# RaspberryMesh.net
KiCad netlist of a schematic drawn in EAGLE
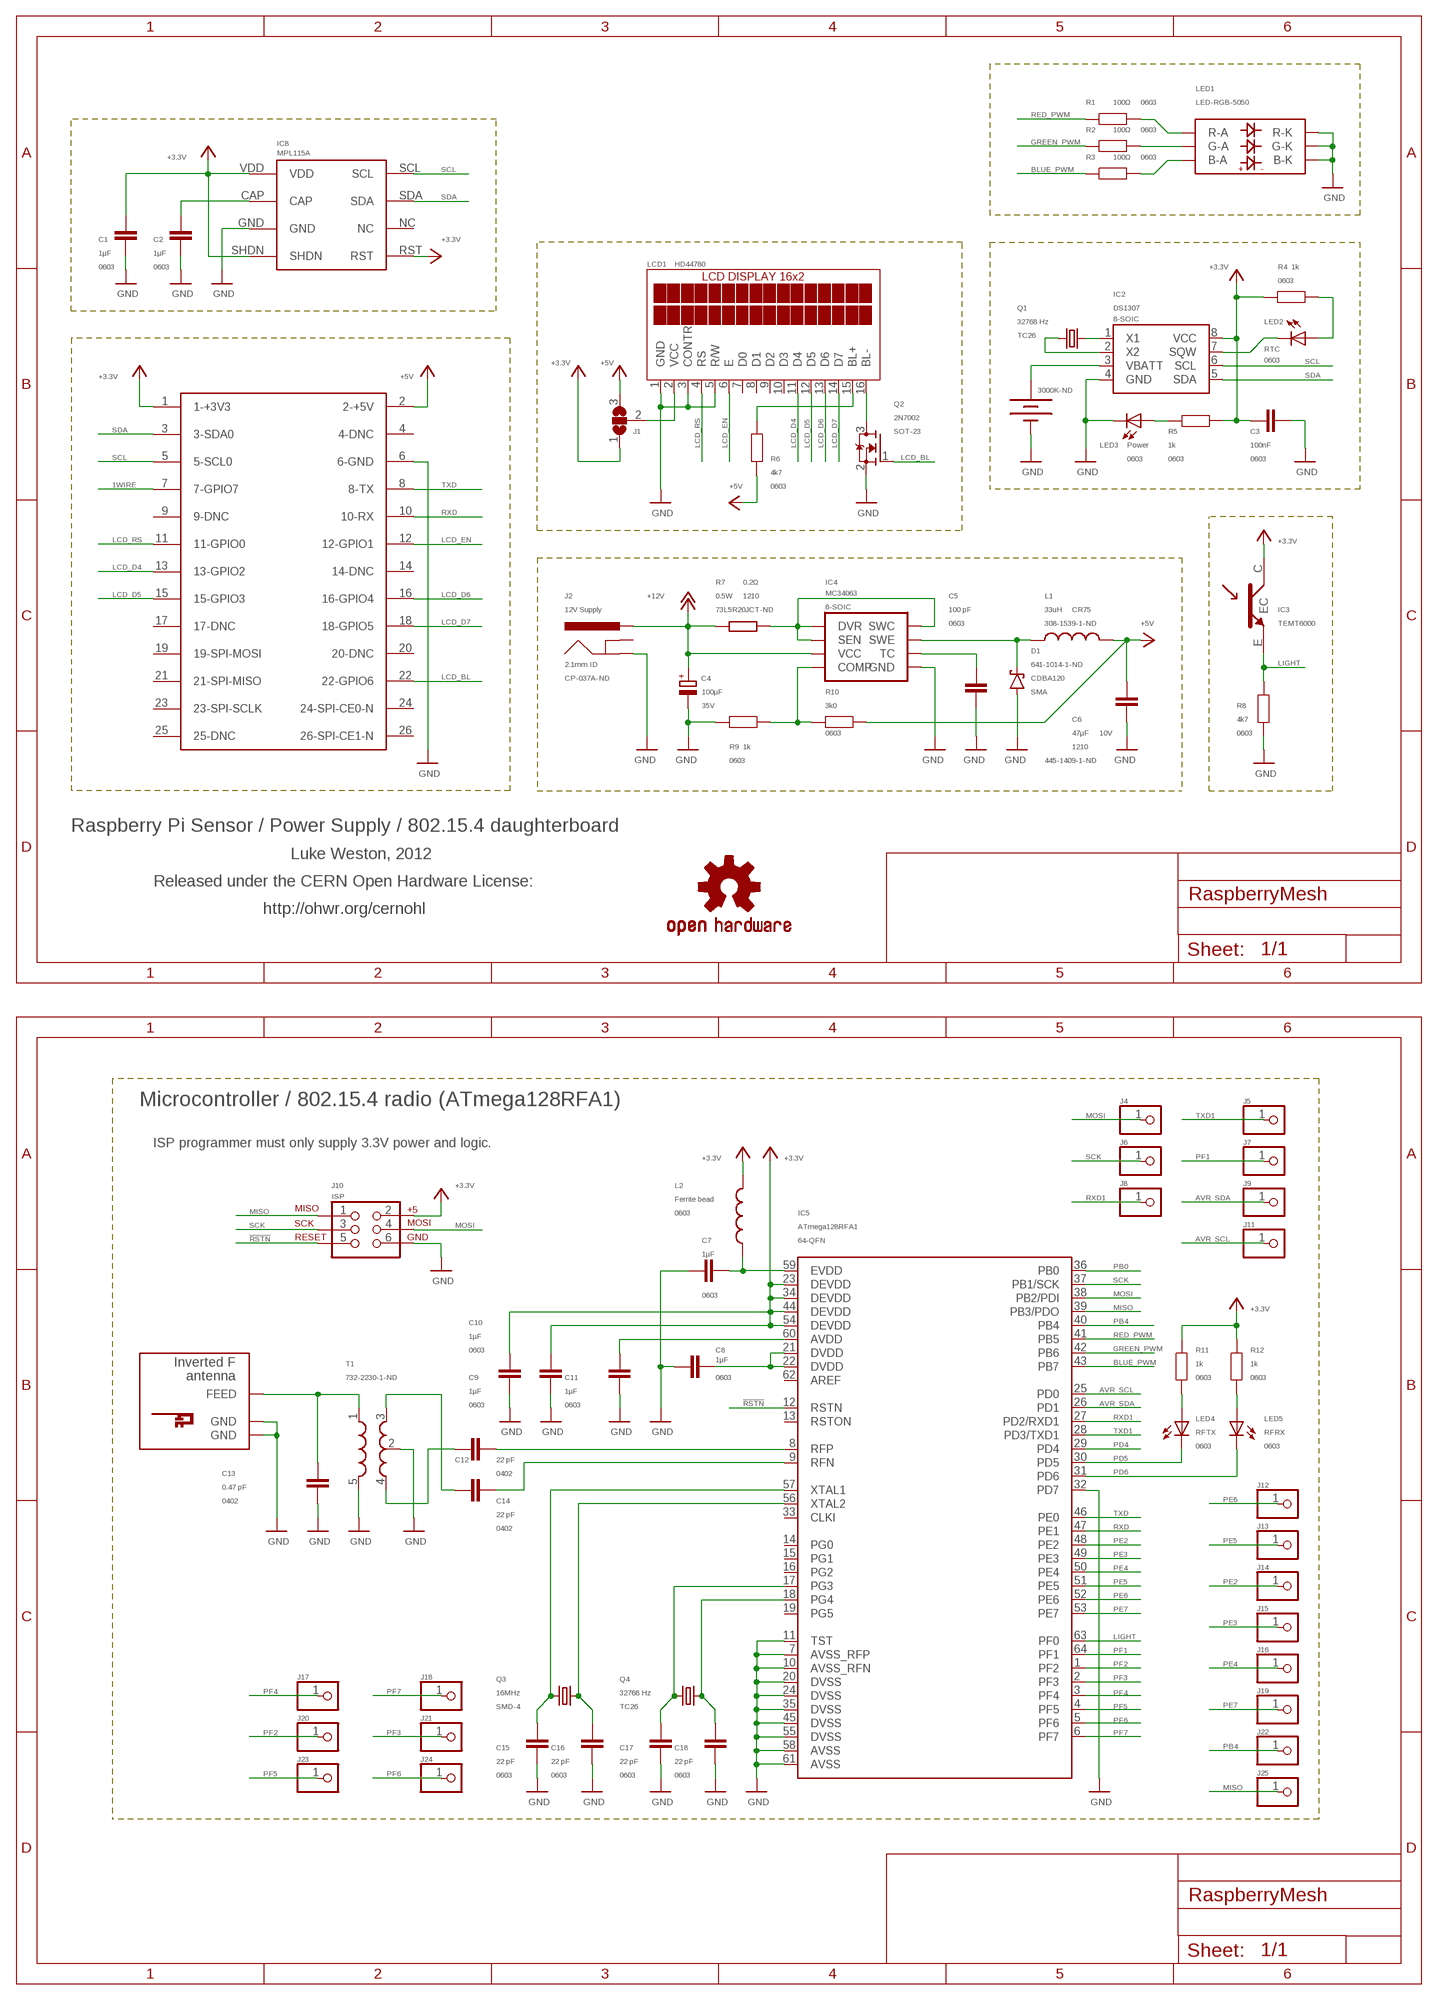
[diagram p0: schematic, sheet 1]

(export (version "E")
  (design (tool "Eeschema 10.0.6"))
  (components
    (comp (ref "A1")
      (value "INVERTED_F_ANTENNA+2")
      (footprint "eagle-import:DN007+2")
      (libsource (lib "eagle-import") (part "INVERTED_F_ANTENNA+2"))
    )
    (comp (ref "B1")
      (value "3000K-ND")
      (footprint "eagle-import:BATTCON_12MM")
      (libsource (lib "eagle-import") (part "BATTERY12MM"))
    )
    (comp (ref "C1")
      (value "1µF")
      (footprint "eagle-import:0603")
      (fields (field (name "PACKAGE") "0603"))
      (libsource (lib "eagle-import") (part "CAP0603"))
    )
    (comp (ref "C2")
      (value "1µF")
      (footprint "eagle-import:0603")
      (fields (field (name "PACKAGE") "0603"))
      (libsource (lib "eagle-import") (part "CAP0603"))
    )
    (comp (ref "C3")
      (value "100nF")
      (footprint "eagle-import:0603")
      (fields (field (name "PACKAGE") "0603"))
      (libsource (lib "eagle-import") (part "CAP0603"))
    )
    (comp (ref "C4")
      (value "100µF")
      (footprint "eagle-import:E2,5-6")
      (fields (field (name "VOLTAGE") "35V"))
      (libsource (lib "eagle-import") (part "CPOL-EUE2.5-6"))
    )
    (comp (ref "C5")
      (value "100 pF")
      (footprint "eagle-import:0603")
      (fields (field (name "PACKAGE") "0603"))
      (libsource (lib "eagle-import") (part "CAP0603"))
    )
    (comp (ref "C6")
      (value "47µF")
      (footprint "eagle-import:C1210")
      (fields
        (field (name "PACKAGE") "1210")
        (field (name "SKU") "445-1409-1-ND")
        (field (name "VOLTAGE") "10V")
      )
      (libsource (lib "eagle-import") (part "C-EUC1210"))
    )
    (comp (ref "C7")
      (value "1µF")
      (footprint "eagle-import:0603")
      (fields (field (name "PACKAGE") "0603"))
      (libsource (lib "eagle-import") (part "CAP0603"))
    )
    (comp (ref "C8")
      (value "1µF")
      (footprint "eagle-import:0603")
      (fields (field (name "PACKAGE") "0603"))
      (libsource (lib "eagle-import") (part "CAP0603"))
    )
    (comp (ref "C9")
      (value "1µF")
      (footprint "eagle-import:0603")
      (fields (field (name "PACKAGE") "0603"))
      (libsource (lib "eagle-import") (part "CAP0603"))
    )
    (comp (ref "C10")
      (value "1µF")
      (footprint "eagle-import:0603")
      (fields (field (name "PACKAGE") "0603"))
      (libsource (lib "eagle-import") (part "CAP0603"))
    )
    (comp (ref "C11")
      (value "1µF")
      (footprint "eagle-import:0603")
      (fields (field (name "PACKAGE") "0603"))
      (libsource (lib "eagle-import") (part "CAP0603"))
    )
    (comp (ref "C12")
      (value "22 pF")
      (footprint "eagle-import:C0402")
      (fields (field (name "PACKAGE") "0402"))
      (libsource (lib "eagle-import") (part "CAP0402"))
    )
    (comp (ref "C13")
      (value "0.47 pF")
      (footprint "eagle-import:C0402")
      (fields (field (name "PACKAGE") "0402"))
      (libsource (lib "eagle-import") (part "CAP0402"))
    )
    (comp (ref "C14")
      (value "22 pF")
      (footprint "eagle-import:C0402")
      (fields (field (name "PACKAGE") "0402"))
      (libsource (lib "eagle-import") (part "CAP0402"))
    )
    (comp (ref "C15")
      (value "22 pF")
      (footprint "eagle-import:0603")
      (fields (field (name "PACKAGE") "0603"))
      (libsource (lib "eagle-import") (part "CAP0603"))
    )
    (comp (ref "C16")
      (value "22 pF")
      (footprint "eagle-import:0603")
      (fields (field (name "PACKAGE") "0603"))
      (libsource (lib "eagle-import") (part "CAP0603"))
    )
    (comp (ref "C17")
      (value "22 pF")
      (footprint "eagle-import:0603")
      (fields (field (name "PACKAGE") "0603"))
      (libsource (lib "eagle-import") (part "CAP0603"))
    )
    (comp (ref "C18")
      (value "22 pF")
      (footprint "eagle-import:0603")
      (fields (field (name "PACKAGE") "0603"))
      (libsource (lib "eagle-import") (part "CAP0603"))
    )
    (comp (ref "D1")
      (value "CDBA120")
      (footprint "eagle-import:SMA")
      (fields (field (name "PACKAGE") "SMA") (field (name "SKU") "641-1014-1-ND"))
      (libsource (lib "eagle-import") (part "SCHOTTKY"))
    )
    (comp (ref "IC1")
      (value "MPL115A")
      (footprint "eagle-import:MPL115A")
      (fields (field (name "NAME2") "IC8") (field (name "VALUE2") "MPL115A"))
      (libsource (lib "eagle-import") (part "MPL115A"))
    )
    (comp (ref "IC2")
      (value "DS1307")
      (footprint "eagle-import:SO08")
      (fields (field (name "PACKAGE") "8-SOIC"))
      (libsource (lib "eagle-import") (part "DS1307SO8"))
    )
    (comp (ref "IC3")
      (value "TEMT6000")
      (footprint "eagle-import:TEMT6000")
      (libsource (lib "eagle-import") (part "TEMT6000SMT"))
    )
    (comp (ref "IC4")
      (value "MC34063")
      (footprint "eagle-import:SO08@1")
      (fields (field (name "PACKAGE") "8-SOIC"))
      (libsource (lib "eagle-import") (part "MC34063SMD"))
    )
    (comp (ref "IC5")
      (value "ATmega128RFA1")
      (footprint "eagle-import:QFN-64")
      (fields (field (name "PACKAGE") "64-QFN"))
      (libsource (lib "eagle-import") (part "ATMEGA128RFA1"))
    )
    (comp (ref "J1")
      (value "SJ2W")
      (footprint "eagle-import:SJ_2")
      (libsource (lib "eagle-import") (part "SJ2W"))
    )
    (comp (ref "J2")
      (value "12V Supply")
      (footprint "eagle-import:POWER_JACK_SLOT")
      (fields (field (name "DIAMETER") "2.1mm ID") (field (name "SKU") "CP-037A-ND"))
      (libsource (lib "eagle-import") (part "POWER_JACKSLT"))
    )
    (comp (ref "J3")
      (value "RASPBERRY-PI")
      (footprint "eagle-import:RASPBERRY-PI")
      (libsource (lib "eagle-import") (part "RASPBERRY-PI"))
    )
    (comp (ref "J4")
      (value "PINHD-1X1")
      (footprint "eagle-import:1X01")
      (libsource (lib "eagle-import") (part "PINHD-1X1"))
    )
    (comp (ref "J5")
      (value "PINHD-1X1")
      (footprint "eagle-import:1X01")
      (libsource (lib "eagle-import") (part "PINHD-1X1"))
    )
    (comp (ref "J6")
      (value "PINHD-1X1")
      (footprint "eagle-import:1X01")
      (libsource (lib "eagle-import") (part "PINHD-1X1"))
    )
    (comp (ref "J7")
      (value "PINHD-1X1")
      (footprint "eagle-import:1X01")
      (libsource (lib "eagle-import") (part "PINHD-1X1"))
    )
    (comp (ref "J8")
      (value "PINHD-1X1")
      (footprint "eagle-import:1X01")
      (libsource (lib "eagle-import") (part "PINHD-1X1"))
    )
    (comp (ref "J9")
      (value "PINHD-1X1")
      (footprint "eagle-import:1X01")
      (libsource (lib "eagle-import") (part "PINHD-1X1"))
    )
    (comp (ref "J10")
      (value "ISP")
      (footprint "eagle-import:2X3-NS")
      (libsource (lib "eagle-import") (part "AVR_SPI_PRG_6NS"))
    )
    (comp (ref "J11")
      (value "PINHD-1X1")
      (footprint "eagle-import:1X01")
      (libsource (lib "eagle-import") (part "PINHD-1X1"))
    )
    (comp (ref "J12")
      (value "PINHD-1X1")
      (footprint "eagle-import:1X01")
      (libsource (lib "eagle-import") (part "PINHD-1X1"))
    )
    (comp (ref "J13")
      (value "PINHD-1X1")
      (footprint "eagle-import:1X01")
      (libsource (lib "eagle-import") (part "PINHD-1X1"))
    )
    (comp (ref "J14")
      (value "PINHD-1X1")
      (footprint "eagle-import:1X01")
      (libsource (lib "eagle-import") (part "PINHD-1X1"))
    )
    (comp (ref "J15")
      (value "PINHD-1X1")
      (footprint "eagle-import:1X01")
      (libsource (lib "eagle-import") (part "PINHD-1X1"))
    )
    (comp (ref "J16")
      (value "PINHD-1X1")
      (footprint "eagle-import:1X01")
      (libsource (lib "eagle-import") (part "PINHD-1X1"))
    )
    (comp (ref "J17")
      (value "PINHD-1X1")
      (footprint "eagle-import:1X01")
      (libsource (lib "eagle-import") (part "PINHD-1X1"))
    )
    (comp (ref "J18")
      (value "PINHD-1X1")
      (footprint "eagle-import:1X01")
      (libsource (lib "eagle-import") (part "PINHD-1X1"))
    )
    (comp (ref "J19")
      (value "PINHD-1X1")
      (footprint "eagle-import:1X01")
      (libsource (lib "eagle-import") (part "PINHD-1X1"))
    )
    (comp (ref "J20")
      (value "PINHD-1X1")
      (footprint "eagle-import:1X01")
      (libsource (lib "eagle-import") (part "PINHD-1X1"))
    )
    (comp (ref "J21")
      (value "PINHD-1X1")
      (footprint "eagle-import:1X01")
      (libsource (lib "eagle-import") (part "PINHD-1X1"))
    )
    (comp (ref "J22")
      (value "PINHD-1X1")
      (footprint "eagle-import:1X01")
      (libsource (lib "eagle-import") (part "PINHD-1X1"))
    )
    (comp (ref "J23")
      (value "PINHD-1X1")
      (footprint "eagle-import:1X01")
      (libsource (lib "eagle-import") (part "PINHD-1X1"))
    )
    (comp (ref "J24")
      (value "PINHD-1X1")
      (footprint "eagle-import:1X01")
      (libsource (lib "eagle-import") (part "PINHD-1X1"))
    )
    (comp (ref "J25")
      (value "PINHD-1X1")
      (footprint "eagle-import:1X01")
      (libsource (lib "eagle-import") (part "PINHD-1X1"))
    )
    (comp (ref "L1")
      (value "33uH")
      (footprint "eagle-import:CR75")
      (fields (field (name "PACKAGE") "CR75") (field (name "SKU") "308-1539-1-ND"))
      (libsource (lib "eagle-import") (part "INDUCTORCR75"))
    )
    (comp (ref "L2")
      (value "Ferrite bead")
      (footprint "eagle-import:0603")
      (fields (field (name "PACKAGE") "0603"))
      (libsource (lib "eagle-import") (part "freetronics-master-v1_INDUCTOR0603"))
    )
    (comp (ref "LCD1")
      (value "HD44780")
      (footprint "eagle-import:LCD_16X2_REAR")
      (libsource (lib "eagle-import") (part "LCD_16X2_NEWLCD_16X2"))
    )
    (comp (ref "LED1")
      (value "LED-RGB-5050")
      (footprint "eagle-import:LED-RGB-5050")
      (libsource (lib "eagle-import") (part "LED-RGB-50505050"))
    )
    (comp (ref "LED2")
      (value "RTC")
      (footprint "eagle-import:LED-0603")
      (fields (field (name "PACKAGE") "0603"))
      (libsource (lib "eagle-import") (part "LED0603"))
    )
    (comp (ref "LED3")
      (value "Power")
      (footprint "eagle-import:LED-0603")
      (fields (field (name "PACKAGE") "0603"))
      (libsource (lib "eagle-import") (part "LED0603"))
    )
    (comp (ref "LED4")
      (value "RFTX")
      (footprint "eagle-import:LED-0603")
      (fields (field (name "PACKAGE") "0603"))
      (libsource (lib "eagle-import") (part "LED0603"))
    )
    (comp (ref "LED5")
      (value "RFRX")
      (footprint "eagle-import:LED-0603")
      (fields (field (name "PACKAGE") "0603"))
      (libsource (lib "eagle-import") (part "LED0603"))
    )
    (comp (ref "Q1")
      (value "32768 Hz")
      (footprint "eagle-import:CRYSTAL-32KHZ-SMD")
      (fields (field (name "PACKAGE") "TC26"))
      (libsource (lib "eagle-import") (part "CRYSTAL32-SMD"))
    )
    (comp (ref "Q2")
      (value "2N7002")
      (footprint "eagle-import:SOT23")
      (fields (field (name "PACKAGE") "SOT-23"))
      (libsource (lib "eagle-import") (part "MOSFET-NREFLOW"))
    )
    (comp (ref "Q3")
      (value "16MHz")
      (footprint "eagle-import:CRYSTAL-SMD-5X3")
      (fields (field (name "PACKAGE") "SMD-4"))
      (libsource (lib "eagle-import") (part "CRYSTAL5X3"))
    )
    (comp (ref "Q4")
      (value "32768 Hz")
      (footprint "eagle-import:CRYSTAL-32KHZ-SMD")
      (fields (field (name "PACKAGE") "TC26"))
      (libsource (lib "eagle-import") (part "CRYSTAL32-SMD"))
    )
    (comp (ref "R1")
      (value "100Ω")
      (footprint "eagle-import:0603")
      (fields (field (name "PACKAGE") "0603"))
      (libsource (lib "eagle-import") (part "RESISTOR0603"))
    )
    (comp (ref "R2")
      (value "100Ω")
      (footprint "eagle-import:0603")
      (fields (field (name "PACKAGE") "0603"))
      (libsource (lib "eagle-import") (part "RESISTOR0603"))
    )
    (comp (ref "R3")
      (value "100Ω")
      (footprint "eagle-import:0603")
      (fields (field (name "PACKAGE") "0603"))
      (libsource (lib "eagle-import") (part "RESISTOR0603"))
    )
    (comp (ref "R4")
      (value "1k")
      (footprint "eagle-import:0603")
      (fields (field (name "PACKAGE") "0603"))
      (libsource (lib "eagle-import") (part "RESISTOR0603"))
    )
    (comp (ref "R5")
      (value "1k")
      (footprint "eagle-import:0603")
      (fields (field (name "PACKAGE") "0603"))
      (libsource (lib "eagle-import") (part "RESISTOR0603"))
    )
    (comp (ref "R6")
      (value "4k7")
      (footprint "eagle-import:0603")
      (fields (field (name "PACKAGE") "0603"))
      (libsource (lib "eagle-import") (part "RESISTOR0603"))
    )
    (comp (ref "R7")
      (value "0.2Ω")
      (footprint "eagle-import:R1210")
      (fields
        (field (name "PACKAGE") "1210")
        (field (name "POWER") "0.5W")
        (field (name "SKU") "73L5R20JCT-ND")
      )
      (libsource (lib "eagle-import") (part "R-EU_R1210"))
    )
    (comp (ref "R8")
      (value "4k7")
      (footprint "eagle-import:0603")
      (fields (field (name "PACKAGE") "0603"))
      (libsource (lib "eagle-import") (part "RESISTOR0603"))
    )
    (comp (ref "R9")
      (value "1k")
      (footprint "eagle-import:0603")
      (fields (field (name "PACKAGE") "0603"))
      (libsource (lib "eagle-import") (part "RESISTOR0603"))
    )
    (comp (ref "R10")
      (value "3k0")
      (footprint "eagle-import:0603")
      (fields (field (name "PACKAGE") "0603"))
      (libsource (lib "eagle-import") (part "RESISTOR0603"))
    )
    (comp (ref "R11")
      (value "1k")
      (footprint "eagle-import:0603")
      (fields (field (name "PACKAGE") "0603"))
      (libsource (lib "eagle-import") (part "RESISTOR0603"))
    )
    (comp (ref "R12")
      (value "1k")
      (footprint "eagle-import:0603")
      (fields (field (name "PACKAGE") "0603"))
      (libsource (lib "eagle-import") (part "RESISTOR0603"))
    )
    (comp (ref "SY1")
      (value "OSHW-LOGOS")
      (footprint "eagle-import:OSHW-LOGO-S")
      (libsource (lib "eagle-import") (part "OSHW-LOGOS"))
    )
    (comp (ref "T1")
      (value "732-2230-1-ND")
      (footprint "eagle-import:BALUN")
      (libsource (lib "eagle-import") (part "BALUN0805"))
    )
  )
  (nets
    (net (code "1") (name "+3.3V") (class "Default")
      (node (ref "C1") (pin "2") (pinfunction "2_2") (pintype "passive"))
      (node (ref "C10") (pin "1") (pinfunction "1_1") (pintype "passive"))
      (node (ref "C3") (pin "1") (pinfunction "1_1") (pintype "passive"))
      (node (ref "C9") (pin "1") (pinfunction "1_1") (pintype "passive"))
      (node (ref "IC1") (pin "RST") (pinfunction "RST_RST") (pintype "bidirectional"))
      (node (ref "IC1") (pin "SHDN") (pinfunction "SHDN_SHDN") (pintype "bidirectional"))
      (node (ref "IC1") (pin "VDD") (pinfunction "VDD_VDD") (pintype "bidirectional"))
      (node (ref "IC2") (pin "8") (pinfunction "VCC_8") (pintype "bidirectional"))
      (node (ref "IC3") (pin "C") (pinfunction "C_C") (pintype "bidirectional"))
      (node (ref "IC5") (pin "23") (pinfunction "DEVDD_23") (pintype "bidirectional"))
      (node (ref "IC5") (pin "34") (pinfunction "DEVDD_34") (pintype "bidirectional"))
      (node (ref "IC5") (pin "44") (pinfunction "DEVDD_44") (pintype "bidirectional"))
      (node (ref "IC5") (pin "54") (pinfunction "DEVDD_54") (pintype "bidirectional"))
      (node (ref "J1") (pin "1") (pinfunction "1_1") (pintype "passive"))
      (node (ref "J10") (pin "2") (pinfunction "2_2") (pintype "passive"))
      (node (ref "J3") (pin "1") (pinfunction "1-+3V3_1") (pintype "bidirectional"))
      (node (ref "L2") (pin "2") (pinfunction "2_2") (pintype "passive"))
      (node (ref "R11") (pin "2") (pinfunction "2_2") (pintype "passive"))
      (node (ref "R12") (pin "2") (pinfunction "2_2") (pintype "passive"))
      (node (ref "R4") (pin "2") (pinfunction "2_2") (pintype "passive"))
      (node (ref "R5") (pin "2") (pinfunction "2_2") (pintype "passive"))
    )
    (net (code "2") (name "+5V") (class "Default")
      (node (ref "C6") (pin "1") (pinfunction "1_1") (pintype "passive"))
      (node (ref "J1") (pin "3") (pinfunction "3_3") (pintype "passive"))
      (node (ref "J3") (pin "2") (pinfunction "2-+5V_2") (pintype "bidirectional"))
      (node (ref "L1") (pin "P$2") (pinfunction "2_P$2") (pintype "passive"))
      (node (ref "R10") (pin "1") (pinfunction "1_1") (pintype "passive"))
      (node (ref "R6") (pin "2") (pinfunction "2_2") (pintype "passive"))
    )
    (net (code "3") (name "+12V") (class "Default")
      (node (ref "C4") (pin "+") (pinfunction "+_+") (pintype "passive"))
      (node (ref "IC4") (pin "6") (pinfunction "VCC_6") (pintype "bidirectional"))
      (node (ref "J2") (pin "PWR") (pinfunction "PWR_PWR") (pintype "bidirectional"))
      (node (ref "R7") (pin "1") (pinfunction "1_1") (pintype "passive"))
    )
    (net (code "4") (name "/1WIRE") (class "Default")
      (node (ref "J3") (pin "7") (pinfunction "7-GPIO7_7") (pintype "bidirectional"))
    )
    (net (code "5") (name "/AVR_SCL") (class "Default")
      (node (ref "IC5") (pin "25") (pinfunction "PD0_25") (pintype "bidirectional"))
      (node (ref "J11") (pin "1") (pinfunction "1_1") (pintype "passive"))
    )
    (net (code "6") (name "/AVR_SDA") (class "Default")
      (node (ref "IC5") (pin "26") (pinfunction "PD1_26") (pintype "bidirectional"))
      (node (ref "J9") (pin "1") (pinfunction "1_1") (pintype "passive"))
    )
    (net (code "7") (name "/BLUE_PWM") (class "Default")
      (node (ref "IC5") (pin "43") (pinfunction "PB7_43") (pintype "bidirectional"))
      (node (ref "R3") (pin "2") (pinfunction "2_2") (pintype "passive"))
    )
    (net (code "8") (name "/GREEN_PWM") (class "Default")
      (node (ref "IC5") (pin "42") (pinfunction "PB6_42") (pintype "bidirectional"))
      (node (ref "R2") (pin "2") (pinfunction "2_2") (pintype "passive"))
    )
    (net (code "9") (name "/LCD_BL") (class "Default")
      (node (ref "J3") (pin "22") (pinfunction "22-GPIO6_22") (pintype "bidirectional"))
      (node (ref "Q2") (pin "1") (pinfunction "G_1") (pintype "bidirectional"))
    )
    (net (code "10") (name "/LCD_D4") (class "Default")
      (node (ref "J3") (pin "13") (pinfunction "13-GPIO2_13") (pintype "bidirectional"))
      (node (ref "LCD1") (pin "11") (pinfunction "D4_11") (pintype "input"))
    )
    (net (code "11") (name "/LCD_D5") (class "Default")
      (node (ref "J3") (pin "15") (pinfunction "15-GPIO3_15") (pintype "bidirectional"))
      (node (ref "LCD1") (pin "12") (pinfunction "D5_12") (pintype "input"))
    )
    (net (code "12") (name "/LCD_D6") (class "Default")
      (node (ref "J3") (pin "16") (pinfunction "16-GPIO4_16") (pintype "bidirectional"))
      (node (ref "LCD1") (pin "13") (pinfunction "D6_13") (pintype "input"))
    )
    (net (code "13") (name "/LCD_D7") (class "Default")
      (node (ref "J3") (pin "18") (pinfunction "18-GPIO5_18") (pintype "bidirectional"))
      (node (ref "LCD1") (pin "14") (pinfunction "D7_14") (pintype "input"))
    )
    (net (code "14") (name "/LCD_EN") (class "Default")
      (node (ref "J3") (pin "12") (pinfunction "12-GPIO1_12") (pintype "bidirectional"))
      (node (ref "LCD1") (pin "6") (pinfunction "E_6") (pintype "input"))
    )
    (net (code "15") (name "/LCD_RS") (class "Default")
      (node (ref "J3") (pin "11") (pinfunction "11-GPIO0_11") (pintype "bidirectional"))
      (node (ref "LCD1") (pin "4") (pinfunction "RS_4") (pintype "input"))
    )
    (net (code "16") (name "/LIGHT") (class "Default")
      (node (ref "IC3") (pin "E") (pinfunction "E_E") (pintype "bidirectional"))
      (node (ref "IC5") (pin "63") (pinfunction "PF0_63") (pintype "bidirectional"))
      (node (ref "R8") (pin "2") (pinfunction "2_2") (pintype "passive"))
    )
    (net (code "17") (name "/MISO") (class "Default")
      (node (ref "IC5") (pin "39") (pinfunction "PB3/PDO_39") (pintype "bidirectional"))
      (node (ref "J10") (pin "1") (pinfunction "1_1") (pintype "passive"))
      (node (ref "J25") (pin "1") (pinfunction "1_1") (pintype "passive"))
    )
    (net (code "18") (name "/MOSI") (class "Default")
      (node (ref "IC5") (pin "38") (pinfunction "PB2/PDI_38") (pintype "bidirectional"))
      (node (ref "J10") (pin "4") (pinfunction "4_4") (pintype "passive"))
      (node (ref "J4") (pin "1") (pinfunction "1_1") (pintype "passive"))
    )
    (net (code "19") (name "/PB0") (class "Default")
      (node (ref "IC5") (pin "36") (pinfunction "PB0_36") (pintype "bidirectional"))
    )
    (net (code "20") (name "/PB4") (class "Default")
      (node (ref "IC5") (pin "40") (pinfunction "PB4_40") (pintype "bidirectional"))
      (node (ref "J22") (pin "1") (pinfunction "1_1") (pintype "passive"))
    )
    (net (code "21") (name "/PD4") (class "Default")
      (node (ref "IC5") (pin "29") (pinfunction "PD4_29") (pintype "bidirectional"))
    )
    (net (code "22") (name "/PD5") (class "Default")
      (node (ref "IC5") (pin "30") (pinfunction "PD5_30") (pintype "bidirectional"))
      (node (ref "LED4") (pin "C") (pinfunction "C_C") (pintype "passive"))
    )
    (net (code "23") (name "/PD6") (class "Default")
      (node (ref "IC5") (pin "31") (pinfunction "PD6_31") (pintype "bidirectional"))
      (node (ref "LED5") (pin "C") (pinfunction "C_C") (pintype "passive"))
    )
    (net (code "24") (name "/PE2") (class "Default")
      (node (ref "IC5") (pin "48") (pinfunction "PE2_48") (pintype "bidirectional"))
      (node (ref "J14") (pin "1") (pinfunction "1_1") (pintype "passive"))
    )
    (net (code "25") (name "/PE3") (class "Default")
      (node (ref "IC5") (pin "49") (pinfunction "PE3_49") (pintype "bidirectional"))
      (node (ref "J15") (pin "1") (pinfunction "1_1") (pintype "passive"))
    )
    (net (code "26") (name "/PE4") (class "Default")
      (node (ref "IC5") (pin "50") (pinfunction "PE4_50") (pintype "bidirectional"))
      (node (ref "J16") (pin "1") (pinfunction "1_1") (pintype "passive"))
    )
    (net (code "27") (name "/PE5") (class "Default")
      (node (ref "IC5") (pin "51") (pinfunction "PE5_51") (pintype "bidirectional"))
      (node (ref "J13") (pin "1") (pinfunction "1_1") (pintype "passive"))
    )
    (net (code "28") (name "/PE6") (class "Default")
      (node (ref "IC5") (pin "52") (pinfunction "PE6_52") (pintype "bidirectional"))
      (node (ref "J12") (pin "1") (pinfunction "1_1") (pintype "passive"))
    )
    (net (code "29") (name "/PE7") (class "Default")
      (node (ref "IC5") (pin "53") (pinfunction "PE7_53") (pintype "bidirectional"))
      (node (ref "J19") (pin "1") (pinfunction "1_1") (pintype "passive"))
    )
    (net (code "30") (name "/PF1") (class "Default")
      (node (ref "IC5") (pin "64") (pinfunction "PF1_64") (pintype "bidirectional"))
      (node (ref "J7") (pin "1") (pinfunction "1_1") (pintype "passive"))
    )
    (net (code "31") (name "/PF2") (class "Default")
      (node (ref "IC5") (pin "1") (pinfunction "PF2_1") (pintype "bidirectional"))
      (node (ref "J20") (pin "1") (pinfunction "1_1") (pintype "passive"))
    )
    (net (code "32") (name "/PF3") (class "Default")
      (node (ref "IC5") (pin "2") (pinfunction "PF3_2") (pintype "bidirectional"))
      (node (ref "J21") (pin "1") (pinfunction "1_1") (pintype "passive"))
    )
    (net (code "33") (name "/PF4") (class "Default")
      (node (ref "IC5") (pin "3") (pinfunction "PF4_3") (pintype "bidirectional"))
      (node (ref "J17") (pin "1") (pinfunction "1_1") (pintype "passive"))
    )
    (net (code "34") (name "/PF5") (class "Default")
      (node (ref "IC5") (pin "4") (pinfunction "PF5_4") (pintype "bidirectional"))
      (node (ref "J23") (pin "1") (pinfunction "1_1") (pintype "passive"))
    )
    (net (code "35") (name "/PF6") (class "Default")
      (node (ref "IC5") (pin "5") (pinfunction "PF6_5") (pintype "bidirectional"))
      (node (ref "J24") (pin "1") (pinfunction "1_1") (pintype "passive"))
    )
    (net (code "36") (name "/PF7") (class "Default")
      (node (ref "IC5") (pin "6") (pinfunction "PF7_6") (pintype "bidirectional"))
      (node (ref "J18") (pin "1") (pinfunction "1_1") (pintype "passive"))
    )
    (net (code "37") (name "/RED_PWM") (class "Default")
      (node (ref "IC5") (pin "41") (pinfunction "PB5_41") (pintype "bidirectional"))
      (node (ref "R1") (pin "2") (pinfunction "2_2") (pintype "passive"))
    )
    (net (code "38") (name "/RXD") (class "Default")
      (node (ref "IC5") (pin "47") (pinfunction "PE1_47") (pintype "bidirectional"))
      (node (ref "J3") (pin "10") (pinfunction "10-RX_10") (pintype "bidirectional"))
    )
    (net (code "39") (name "/RXD1") (class "Default")
      (node (ref "IC5") (pin "27") (pinfunction "PD2/RXD1_27") (pintype "bidirectional"))
      (node (ref "J8") (pin "1") (pinfunction "1_1") (pintype "passive"))
    )
    (net (code "40") (name "/SCK") (class "Default")
      (node (ref "IC5") (pin "37") (pinfunction "PB1/SCK_37") (pintype "bidirectional"))
      (node (ref "J10") (pin "3") (pinfunction "3_3") (pintype "passive"))
      (node (ref "J6") (pin "1") (pinfunction "1_1") (pintype "passive"))
    )
    (net (code "41") (name "/SCL") (class "Default")
      (node (ref "IC1") (pin "SCL") (pinfunction "SCL_SCL") (pintype "bidirectional"))
      (node (ref "IC2") (pin "6") (pinfunction "SCL_6") (pintype "bidirectional"))
      (node (ref "J3") (pin "5") (pinfunction "5-SCL0_5") (pintype "bidirectional"))
    )
    (net (code "42") (name "/SDA") (class "Default")
      (node (ref "IC1") (pin "SDA") (pinfunction "SDA_SDA") (pintype "bidirectional"))
      (node (ref "IC2") (pin "5") (pinfunction "SDA_5") (pintype "bidirectional"))
      (node (ref "J3") (pin "3") (pinfunction "3-SDA0_3") (pintype "bidirectional"))
    )
    (net (code "43") (name "/TXD") (class "Default")
      (node (ref "IC5") (pin "46") (pinfunction "PE0_46") (pintype "bidirectional"))
      (node (ref "J3") (pin "8") (pinfunction "8-TX_8") (pintype "bidirectional"))
    )
    (net (code "44") (name "/TXD1") (class "Default")
      (node (ref "IC5") (pin "28") (pinfunction "PD3/TXD1_28") (pintype "bidirectional"))
      (node (ref "J5") (pin "1") (pinfunction "1_1") (pintype "passive"))
    )
    (net (code "45") (name "/~{RSTN}") (class "Default")
      (node (ref "IC5") (pin "12") (pinfunction "RSTN_12") (pintype "bidirectional"))
      (node (ref "J10") (pin "5") (pinfunction "5_5") (pintype "passive"))
    )
    (net (code "46") (name "GND") (class "Default")
      (node (ref "A1") (pin "GND") (pinfunction "GND_GND") (pintype "bidirectional"))
      (node (ref "A1") (pin "GND@1") (pinfunction "GND_GND@1") (pintype "bidirectional"))
      (node (ref "B1") (pin "GND") (pinfunction "-_GND") (pintype "power_in"))
      (node (ref "C1") (pin "1") (pinfunction "1_1") (pintype "passive"))
      (node (ref "C10") (pin "2") (pinfunction "2_2") (pintype "passive"))
      (node (ref "C11") (pin "2") (pinfunction "2_2") (pintype "passive"))
      (node (ref "C13") (pin "2") (pinfunction "2_2") (pintype "passive"))
      (node (ref "C15") (pin "1") (pinfunction "1_1") (pintype "passive"))
      (node (ref "C16") (pin "1") (pinfunction "1_1") (pintype "passive"))
      (node (ref "C17") (pin "1") (pinfunction "1_1") (pintype "passive"))
      (node (ref "C18") (pin "1") (pinfunction "1_1") (pintype "passive"))
      (node (ref "C2") (pin "1") (pinfunction "1_1") (pintype "passive"))
      (node (ref "C3") (pin "2") (pinfunction "2_2") (pintype "passive"))
      (node (ref "C4") (pin "-") (pinfunction "-_-") (pintype "passive"))
      (node (ref "C5") (pin "2") (pinfunction "2_2") (pintype "passive"))
      (node (ref "C6") (pin "2") (pinfunction "2_2") (pintype "passive"))
      (node (ref "C7") (pin "2") (pinfunction "2_2") (pintype "passive"))
      (node (ref "C8") (pin "2") (pinfunction "2_2") (pintype "passive"))
      (node (ref "C9") (pin "2") (pinfunction "2_2") (pintype "passive"))
      (node (ref "D1") (pin "A") (pinfunction "A_A") (pintype "passive"))
      (node (ref "IC1") (pin "GND") (pinfunction "GND_GND") (pintype "bidirectional"))
      (node (ref "IC2") (pin "4") (pinfunction "GND_4") (pintype "bidirectional"))
      (node (ref "IC4") (pin "4") (pinfunction "GND_4") (pintype "bidirectional"))
      (node (ref "IC5") (pin "10") (pinfunction "AVSS_RFN_10") (pintype "bidirectional"))
      (node (ref "IC5") (pin "11") (pinfunction "TST_11") (pintype "bidirectional"))
      (node (ref "IC5") (pin "20") (pinfunction "DVSS_20") (pintype "bidirectional"))
      (node (ref "IC5") (pin "24") (pinfunction "DVSS_24") (pintype "bidirectional"))
      (node (ref "IC5") (pin "32") (pinfunction "PD7_32") (pintype "bidirectional"))
      (node (ref "IC5") (pin "35") (pinfunction "DVSS_35") (pintype "bidirectional"))
      (node (ref "IC5") (pin "45") (pinfunction "DVSS_45") (pintype "bidirectional"))
      (node (ref "IC5") (pin "55") (pinfunction "DVSS_55") (pintype "bidirectional"))
      (node (ref "IC5") (pin "58") (pinfunction "AVSS_58") (pintype "bidirectional"))
      (node (ref "IC5") (pin "61") (pinfunction "AVSS_61") (pintype "bidirectional"))
      (node (ref "IC5") (pin "7") (pinfunction "AVSS_RFP_7") (pintype "bidirectional"))
      (node (ref "J10") (pin "6") (pinfunction "6_6") (pintype "passive"))
      (node (ref "J2") (pin "GND") (pinfunction "GND_GND") (pintype "bidirectional"))
      (node (ref "J3") (pin "6") (pinfunction "6-GND_6") (pintype "bidirectional"))
      (node (ref "LCD1") (pin "1") (pinfunction "GND_1") (pintype "power_in"))
      (node (ref "LCD1") (pin "3") (pinfunction "CONTR_3") (pintype "input"))
      (node (ref "LCD1") (pin "5") (pinfunction "R/W_5") (pintype "input"))
      (node (ref "LED1") (pin "BK") (pinfunction "B-K_BK") (pintype "bidirectional"))
      (node (ref "LED1") (pin "GK") (pinfunction "G-K_GK") (pintype "bidirectional"))
      (node (ref "LED1") (pin "RK") (pinfunction "R-K_RK") (pintype "bidirectional"))
      (node (ref "LED3") (pin "C") (pinfunction "C_C") (pintype "passive"))
      (node (ref "Q2") (pin "2") (pinfunction "S_2") (pintype "bidirectional"))
      (node (ref "R8") (pin "1") (pinfunction "1_1") (pintype "passive"))
      (node (ref "R9") (pin "2") (pinfunction "2_2") (pintype "passive"))
      (node (ref "T1") (pin "2") (pinfunction "GND_2") (pintype "bidirectional"))
      (node (ref "T1") (pin "5") (pinfunction "GND_5") (pintype "bidirectional"))
    )
    (net (code "47") (name "Net-(B1-+)") (class "Default")
      (node (ref "B1") (pin "PWR@1") (pinfunction "+_PWR@1") (pintype "power_in"))
      (node (ref "IC2") (pin "3") (pinfunction "VBATT_3") (pintype "bidirectional"))
    )
    (net (code "48") (name "Net-(C2-Pad2)") (class "Default")
      (node (ref "C2") (pin "2") (pinfunction "2_2") (pintype "passive"))
      (node (ref "IC1") (pin "CAP") (pinfunction "CAP_CAP") (pintype "bidirectional"))
    )
    (net (code "49") (name "Net-(C8-Pad1)") (class "Default")
      (node (ref "C8") (pin "1") (pinfunction "1_1") (pintype "passive"))
      (node (ref "IC5") (pin "21") (pinfunction "DVDD_21") (pintype "bidirectional"))
      (node (ref "IC5") (pin "22") (pinfunction "DVDD_22") (pintype "bidirectional"))
    )
    (net (code "50") (name "Net-(IC2-SQW)") (class "Default")
      (node (ref "IC2") (pin "7") (pinfunction "SQW_7") (pintype "bidirectional"))
      (node (ref "LED2") (pin "C") (pinfunction "C_C") (pintype "passive"))
    )
    (net (code "51") (name "Net-(IC2-X1)") (class "Default")
      (node (ref "IC2") (pin "1") (pinfunction "X1_1") (pintype "bidirectional"))
      (node (ref "Q1") (pin "X2") (pinfunction "2_X2") (pintype "passive"))
    )
    (net (code "52") (name "Net-(IC2-X2)") (class "Default")
      (node (ref "IC2") (pin "2") (pinfunction "X2_2") (pintype "bidirectional"))
      (node (ref "Q1") (pin "X1") (pinfunction "1_X1") (pintype "passive"))
    )
    (net (code "53") (name "Net-(IC4-COMP)") (class "Default")
      (node (ref "IC4") (pin "5") (pinfunction "COMP_5") (pintype "bidirectional"))
      (node (ref "R10") (pin "2") (pinfunction "2_2") (pintype "passive"))
      (node (ref "R9") (pin "1") (pinfunction "1_1") (pintype "passive"))
    )
    (net (code "54") (name "Net-(IC4-DVR)") (class "Default")
      (node (ref "IC4") (pin "1") (pinfunction "SWC_1") (pintype "bidirectional"))
      (node (ref "IC4") (pin "7") (pinfunction "SEN_7") (pintype "bidirectional"))
      (node (ref "IC4") (pin "8") (pinfunction "DVR_8") (pintype "bidirectional"))
      (node (ref "R7") (pin "2") (pinfunction "2_2") (pintype "passive"))
    )
    (net (code "55") (name "Net-(IC4-SWE)") (class "Default")
      (node (ref "D1") (pin "K") (pinfunction "K_K") (pintype "passive"))
      (node (ref "IC4") (pin "2") (pinfunction "SWE_2") (pintype "bidirectional"))
      (node (ref "L1") (pin "P$1") (pinfunction "1_P$1") (pintype "passive"))
    )
    (net (code "56") (name "Net-(IC4-TC)") (class "Default")
      (node (ref "C5") (pin "1") (pinfunction "1_1") (pintype "passive"))
      (node (ref "IC4") (pin "3") (pinfunction "TC_3") (pintype "bidirectional"))
    )
    (net (code "57") (name "Net-(IC5-AVDD)") (class "Default")
      (node (ref "C11") (pin "1") (pinfunction "1_1") (pintype "passive"))
      (node (ref "IC5") (pin "60") (pinfunction "AVDD_60") (pintype "bidirectional"))
    )
    (net (code "58") (name "Net-(IC5-EVDD)") (class "Default")
      (node (ref "C7") (pin "1") (pinfunction "1_1") (pintype "passive"))
      (node (ref "IC5") (pin "59") (pinfunction "EVDD_59") (pintype "bidirectional"))
      (node (ref "L2") (pin "1") (pinfunction "1_1") (pintype "passive"))
    )
    (net (code "59") (name "Net-(IC5-PG3)") (class "Default")
      (node (ref "C17") (pin "2") (pinfunction "2_2") (pintype "passive"))
      (node (ref "IC5") (pin "17") (pinfunction "PG3_17") (pintype "bidirectional"))
      (node (ref "Q4") (pin "X1") (pinfunction "1_X1") (pintype "passive"))
    )
    (net (code "60") (name "Net-(IC5-PG4)") (class "Default")
      (node (ref "C18") (pin "2") (pinfunction "2_2") (pintype "passive"))
      (node (ref "IC5") (pin "18") (pinfunction "PG4_18") (pintype "bidirectional"))
      (node (ref "Q4") (pin "X2") (pinfunction "2_X2") (pintype "passive"))
    )
    (net (code "61") (name "Net-(IC5-RFN)") (class "Default")
      (node (ref "C14") (pin "1") (pinfunction "1_1") (pintype "passive"))
      (node (ref "IC5") (pin "9") (pinfunction "RFN_9") (pintype "bidirectional"))
    )
    (net (code "62") (name "Net-(IC5-RFP)") (class "Default")
      (node (ref "C12") (pin "1") (pinfunction "1_1") (pintype "passive"))
      (node (ref "IC5") (pin "8") (pinfunction "RFP_8") (pintype "bidirectional"))
    )
    (net (code "63") (name "Net-(IC5-XTAL1)") (class "Default")
      (node (ref "C15") (pin "2") (pinfunction "2_2") (pintype "passive"))
      (node (ref "IC5") (pin "57") (pinfunction "XTAL1_57") (pintype "bidirectional"))
      (node (ref "Q3") (pin "1") (pinfunction "1_1") (pintype "passive"))
    )
    (net (code "64") (name "Net-(IC5-XTAL2)") (class "Default")
      (node (ref "C16") (pin "2") (pinfunction "2_2") (pintype "passive"))
      (node (ref "IC5") (pin "56") (pinfunction "XTAL2_56") (pintype "bidirectional"))
      (node (ref "Q3") (pin "3") (pinfunction "2_3") (pintype "passive"))
    )
    (net (code "65") (name "Net-(LCD1-BL+)") (class "Default")
      (node (ref "LCD1") (pin "15") (pinfunction "BL+_15") (pintype "input"))
      (node (ref "R6") (pin "1") (pinfunction "1_1") (pintype "passive"))
    )
    (net (code "66") (name "Net-(LCD1-BL-)") (class "Default")
      (node (ref "LCD1") (pin "16") (pinfunction "BL-_16") (pintype "input"))
      (node (ref "Q2") (pin "3") (pinfunction "D_3") (pintype "bidirectional"))
    )
    (net (code "67") (name "Net-(LCD1-VCC)") (class "Default")
      (node (ref "J1") (pin "2") (pinfunction "2_2") (pintype "passive"))
      (node (ref "LCD1") (pin "2") (pinfunction "VCC_2") (pintype "power_in"))
    )
    (net (code "68") (name "Net-(LED1-B-A)") (class "Default")
      (node (ref "LED1") (pin "BA") (pinfunction "B-A_BA") (pintype "bidirectional"))
      (node (ref "R3") (pin "1") (pinfunction "1_1") (pintype "passive"))
    )
    (net (code "69") (name "Net-(LED1-G-A)") (class "Default")
      (node (ref "LED1") (pin "GA") (pinfunction "G-A_GA") (pintype "bidirectional"))
      (node (ref "R2") (pin "1") (pinfunction "1_1") (pintype "passive"))
    )
    (net (code "70") (name "Net-(LED1-R-A)") (class "Default")
      (node (ref "LED1") (pin "RA") (pinfunction "R-A_RA") (pintype "bidirectional"))
      (node (ref "R1") (pin "1") (pinfunction "1_1") (pintype "passive"))
    )
    (net (code "71") (name "Net-(LED2-PadA)") (class "Default")
      (node (ref "LED2") (pin "A") (pinfunction "A_A") (pintype "passive"))
      (node (ref "R4") (pin "1") (pinfunction "1_1") (pintype "passive"))
    )
    (net (code "72") (name "Net-(LED3-PadA)") (class "Default")
      (node (ref "LED3") (pin "A") (pinfunction "A_A") (pintype "passive"))
      (node (ref "R5") (pin "1") (pinfunction "1_1") (pintype "passive"))
    )
    (net (code "73") (name "Net-(LED4-PadA)") (class "Default")
      (node (ref "LED4") (pin "A") (pinfunction "A_A") (pintype "passive"))
      (node (ref "R11") (pin "1") (pinfunction "1_1") (pintype "passive"))
    )
    (net (code "74") (name "Net-(LED5-PadA)") (class "Default")
      (node (ref "LED5") (pin "A") (pinfunction "A_A") (pintype "passive"))
      (node (ref "R12") (pin "1") (pinfunction "1_1") (pintype "passive"))
    )
    (net (code "75") (name "Net-(T1-IN)") (class "Default")
      (node (ref "A1") (pin "FEED") (pinfunction "FEED_FEED") (pintype "bidirectional"))
      (node (ref "C13") (pin "1") (pinfunction "1_1") (pintype "passive"))
      (node (ref "T1") (pin "1") (pinfunction "IN_1") (pintype "bidirectional"))
    )
    (net (code "76") (name "Net-(T1-OUT1)") (class "Default")
      (node (ref "C14") (pin "2") (pinfunction "2_2") (pintype "passive"))
      (node (ref "T1") (pin "3") (pinfunction "OUT1_3") (pintype "bidirectional"))
    )
    (net (code "77") (name "Net-(T1-OUT2)") (class "Default")
      (node (ref "C12") (pin "2") (pinfunction "2_2") (pintype "passive"))
      (node (ref "T1") (pin "4") (pinfunction "OUT2_4") (pintype "bidirectional"))
    )
    (net (code "78") (name "unconnected-(IC1-PadNC)") (class "Default")
      (node (ref "IC1") (pin "NC") (pinfunction "NC_NC") (pintype "bidirectional"))
    )
    (net (code "79") (name "unconnected-(IC5-AREF-Pad62)") (class "Default")
      (node (ref "IC5") (pin "62") (pinfunction "AREF_62") (pintype "bidirectional"))
    )
    (net (code "80") (name "unconnected-(IC5-CLKI-Pad33)") (class "Default")
      (node (ref "IC5") (pin "33") (pinfunction "CLKI_33") (pintype "bidirectional"))
    )
    (net (code "81") (name "unconnected-(IC5-PG0-Pad14)") (class "Default")
      (node (ref "IC5") (pin "14") (pinfunction "PG0_14") (pintype "bidirectional"))
    )
    (net (code "82") (name "unconnected-(IC5-PG1-Pad15)") (class "Default")
      (node (ref "IC5") (pin "15") (pinfunction "PG1_15") (pintype "bidirectional"))
    )
    (net (code "83") (name "unconnected-(IC5-PG2-Pad16)") (class "Default")
      (node (ref "IC5") (pin "16") (pinfunction "PG2_16") (pintype "bidirectional"))
    )
    (net (code "84") (name "unconnected-(IC5-PG5-Pad19)") (class "Default")
      (node (ref "IC5") (pin "19") (pinfunction "PG5_19") (pintype "bidirectional"))
    )
    (net (code "85") (name "unconnected-(IC5-RSTON-Pad13)") (class "Default")
      (node (ref "IC5") (pin "13") (pinfunction "RSTON_13") (pintype "bidirectional"))
    )
    (net (code "86") (name "unconnected-(J2-GNDBREAK-PadSW)") (class "Default")
      (node (ref "J2") (pin "SW") (pinfunction "GNDBREAK_SW") (pintype "bidirectional"))
    )
    (net (code "87") (name "unconnected-(J3-4-DNC-Pad4)") (class "Default")
      (node (ref "J3") (pin "4") (pinfunction "4-DNC_4") (pintype "bidirectional"))
    )
    (net (code "88") (name "unconnected-(J3-9-DNC-Pad9)") (class "Default")
      (node (ref "J3") (pin "9") (pinfunction "9-DNC_9") (pintype "bidirectional"))
    )
    (net (code "89") (name "unconnected-(J3-14-DNC-Pad14)") (class "Default")
      (node (ref "J3") (pin "14") (pinfunction "14-DNC_14") (pintype "bidirectional"))
    )
    (net (code "90") (name "unconnected-(J3-17-DNC-Pad17)") (class "Default")
      (node (ref "J3") (pin "17") (pinfunction "17-DNC_17") (pintype "bidirectional"))
    )
    (net (code "91") (name "unconnected-(J3-19-SPI-MOSI-Pad19)") (class "Default")
      (node (ref "J3") (pin "19") (pinfunction "19-SPI-MOSI_19") (pintype "bidirectional"))
    )
    (net (code "92") (name "unconnected-(J3-20-DNC-Pad20)") (class "Default")
      (node (ref "J3") (pin "20") (pinfunction "20-DNC_20") (pintype "bidirectional"))
    )
    (net (code "93") (name "unconnected-(J3-21-SPI-MISO-Pad21)") (class "Default")
      (node (ref "J3") (pin "21") (pinfunction "21-SPI-MISO_21") (pintype "bidirectional"))
    )
    (net (code "94") (name "unconnected-(J3-23-SPI-SCLK-Pad23)") (class "Default")
      (node (ref "J3") (pin "23") (pinfunction "23-SPI-SCLK_23") (pintype "bidirectional"))
    )
    (net (code "95") (name "unconnected-(J3-24-SPI-CE0-N-Pad24)") (class "Default")
      (node (ref "J3") (pin "24") (pinfunction "24-SPI-CE0-N_24") (pintype "bidirectional"))
    )
    (net (code "96") (name "unconnected-(J3-25-DNC-Pad25)") (class "Default")
      (node (ref "J3") (pin "25") (pinfunction "25-DNC_25") (pintype "bidirectional"))
    )
    (net (code "97") (name "unconnected-(J3-26-SPI-CE1-N-Pad26)") (class "Default")
      (node (ref "J3") (pin "26") (pinfunction "26-SPI-CE1-N_26") (pintype "bidirectional"))
    )
    (net (code "98") (name "unconnected-(LCD1-D0-Pad7)") (class "Default")
      (node (ref "LCD1") (pin "7") (pinfunction "D0_7") (pintype "input"))
    )
    (net (code "99") (name "unconnected-(LCD1-D1-Pad8)") (class "Default")
      (node (ref "LCD1") (pin "8") (pinfunction "D1_8") (pintype "input"))
    )
    (net (code "100") (name "unconnected-(LCD1-D2-Pad9)") (class "Default")
      (node (ref "LCD1") (pin "9") (pinfunction "D2_9") (pintype "input"))
    )
    (net (code "101") (name "unconnected-(LCD1-D3-Pad10)") (class "Default")
      (node (ref "LCD1") (pin "10") (pinfunction "D3_10") (pintype "input"))
    )
  )
)
